# ALU-AB.net
KiCad netlist of a schematic drawn in EAGLE
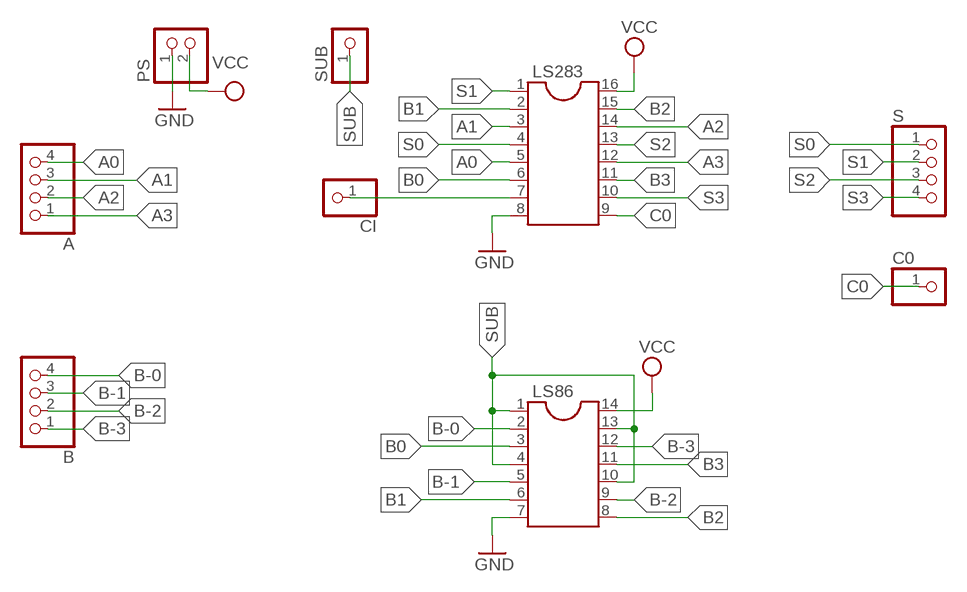
[diagram p0: schematic, sheet 1]

(export (version "E")
  (design (tool "Eeschema 10.0.6"))
  (components
    (comp (ref "A")
      (value "PINHD-1X4")
      (footprint "eagle-import:1X04")
      (libsource (lib "eagle-import") (part "PINHD-1X4"))
    )
    (comp (ref "B")
      (value "PINHD-1X4")
      (footprint "eagle-import:1X04")
      (libsource (lib "eagle-import") (part "PINHD-1X4"))
    )
    (comp (ref "C0")
      (value "PINHD-1X1")
      (footprint "eagle-import:1X01")
      (libsource (lib "eagle-import") (part "PINHD-1X1"))
    )
    (comp (ref "CI")
      (value "PINHD-1X1")
      (footprint "eagle-import:1X01")
      (libsource (lib "eagle-import") (part "PINHD-1X1"))
    )
    (comp (ref "LS86")
      (value "DIL14S")
      (footprint "eagle-import:SOCKET-14")
      (libsource (lib "eagle-import") (part "DIL14S"))
    )
    (comp (ref "LS283")
      (value "DIL16S")
      (footprint "eagle-import:SOCKET-16")
      (libsource (lib "eagle-import") (part "DIL16S"))
    )
    (comp (ref "PS")
      (value "PINHD-1X2")
      (footprint "eagle-import:1X02")
      (libsource (lib "eagle-import") (part "PINHD-1X2"))
    )
    (comp (ref "S")
      (value "PINHD-1X4")
      (footprint "eagle-import:1X04")
      (libsource (lib "eagle-import") (part "PINHD-1X4"))
    )
    (comp (ref "SUB")
      (value "PINHD-1X1")
      (footprint "eagle-import:1X01")
      (libsource (lib "eagle-import") (part "PINHD-1X1"))
    )
  )
  (nets
    (net (code "1") (name "A0") (class "Default")
      (node (ref "A") (pin "4") (pinfunction "4_4") (pintype "passive"))
      (node (ref "LS283") (pin "5") (pinfunction "5_5") (pintype "passive"))
    )
    (net (code "2") (name "A1") (class "Default")
      (node (ref "A") (pin "3") (pinfunction "3_3") (pintype "passive"))
      (node (ref "LS283") (pin "3") (pinfunction "3_3") (pintype "passive"))
    )
    (net (code "3") (name "A2") (class "Default")
      (node (ref "A") (pin "2") (pinfunction "2_2") (pintype "passive"))
      (node (ref "LS283") (pin "14") (pinfunction "14_14") (pintype "passive"))
    )
    (net (code "4") (name "A3") (class "Default")
      (node (ref "A") (pin "1") (pinfunction "1_1") (pintype "passive"))
      (node (ref "LS283") (pin "12") (pinfunction "12_12") (pintype "passive"))
    )
    (net (code "5") (name "B-0") (class "Default")
      (node (ref "B") (pin "4") (pinfunction "4_4") (pintype "passive"))
      (node (ref "LS86") (pin "2") (pinfunction "2_2") (pintype "passive"))
    )
    (net (code "6") (name "B-1") (class "Default")
      (node (ref "B") (pin "3") (pinfunction "3_3") (pintype "passive"))
      (node (ref "LS86") (pin "5") (pinfunction "5_5") (pintype "passive"))
    )
    (net (code "7") (name "B-2") (class "Default")
      (node (ref "B") (pin "2") (pinfunction "2_2") (pintype "passive"))
      (node (ref "LS86") (pin "9") (pinfunction "9_9") (pintype "passive"))
    )
    (net (code "8") (name "B-3") (class "Default")
      (node (ref "B") (pin "1") (pinfunction "1_1") (pintype "passive"))
      (node (ref "LS86") (pin "12") (pinfunction "12_12") (pintype "passive"))
    )
    (net (code "9") (name "B0") (class "Default")
      (node (ref "LS283") (pin "6") (pinfunction "6_6") (pintype "passive"))
      (node (ref "LS86") (pin "3") (pinfunction "3_3") (pintype "passive"))
    )
    (net (code "10") (name "B1") (class "Default")
      (node (ref "LS283") (pin "2") (pinfunction "2_2") (pintype "passive"))
      (node (ref "LS86") (pin "6") (pinfunction "6_6") (pintype "passive"))
    )
    (net (code "11") (name "B2") (class "Default")
      (node (ref "LS283") (pin "15") (pinfunction "15_15") (pintype "passive"))
      (node (ref "LS86") (pin "8") (pinfunction "8_8") (pintype "passive"))
    )
    (net (code "12") (name "B3") (class "Default")
      (node (ref "LS283") (pin "11") (pinfunction "11_11") (pintype "passive"))
      (node (ref "LS86") (pin "11") (pinfunction "11_11") (pintype "passive"))
    )
    (net (code "13") (name "C0") (class "Default")
      (node (ref "C0") (pin "1") (pinfunction "1_1") (pintype "passive"))
      (node (ref "LS283") (pin "9") (pinfunction "9_9") (pintype "passive"))
    )
    (net (code "14") (name "GND") (class "Default")
      (node (ref "LS283") (pin "8") (pinfunction "8_8") (pintype "passive"))
      (node (ref "LS86") (pin "7") (pinfunction "7_7") (pintype "passive"))
      (node (ref "PS") (pin "1") (pinfunction "1_1") (pintype "passive"))
    )
    (net (code "15") (name "Net-(CI-Pad1)") (class "Default")
      (node (ref "CI") (pin "1") (pinfunction "1_1") (pintype "passive"))
      (node (ref "LS283") (pin "7") (pinfunction "7_7") (pintype "passive"))
    )
    (net (code "16") (name "S0") (class "Default")
      (node (ref "LS283") (pin "4") (pinfunction "4_4") (pintype "passive"))
      (node (ref "S") (pin "1") (pinfunction "1_1") (pintype "passive"))
    )
    (net (code "17") (name "S1") (class "Default")
      (node (ref "LS283") (pin "1") (pinfunction "1_1") (pintype "passive"))
      (node (ref "S") (pin "2") (pinfunction "2_2") (pintype "passive"))
    )
    (net (code "18") (name "S2") (class "Default")
      (node (ref "LS283") (pin "13") (pinfunction "13_13") (pintype "passive"))
      (node (ref "S") (pin "3") (pinfunction "3_3") (pintype "passive"))
    )
    (net (code "19") (name "S3") (class "Default")
      (node (ref "LS283") (pin "10") (pinfunction "10_10") (pintype "passive"))
      (node (ref "S") (pin "4") (pinfunction "4_4") (pintype "passive"))
    )
    (net (code "20") (name "SUB") (class "Default")
      (node (ref "LS86") (pin "1") (pinfunction "1_1") (pintype "passive"))
      (node (ref "LS86") (pin "10") (pinfunction "10_10") (pintype "passive"))
      (node (ref "LS86") (pin "13") (pinfunction "13_13") (pintype "passive"))
      (node (ref "LS86") (pin "4") (pinfunction "4_4") (pintype "passive"))
      (node (ref "SUB") (pin "1") (pinfunction "1_1") (pintype "passive"))
    )
    (net (code "21") (name "VCC") (class "Default")
      (node (ref "LS283") (pin "16") (pinfunction "16_16") (pintype "passive"))
      (node (ref "LS86") (pin "14") (pinfunction "14_14") (pintype "passive"))
      (node (ref "PS") (pin "2") (pinfunction "2_2") (pintype "passive"))
    )
  )
)
